# BusBoard.net
KiCad netlist of a schematic drawn in EAGLE
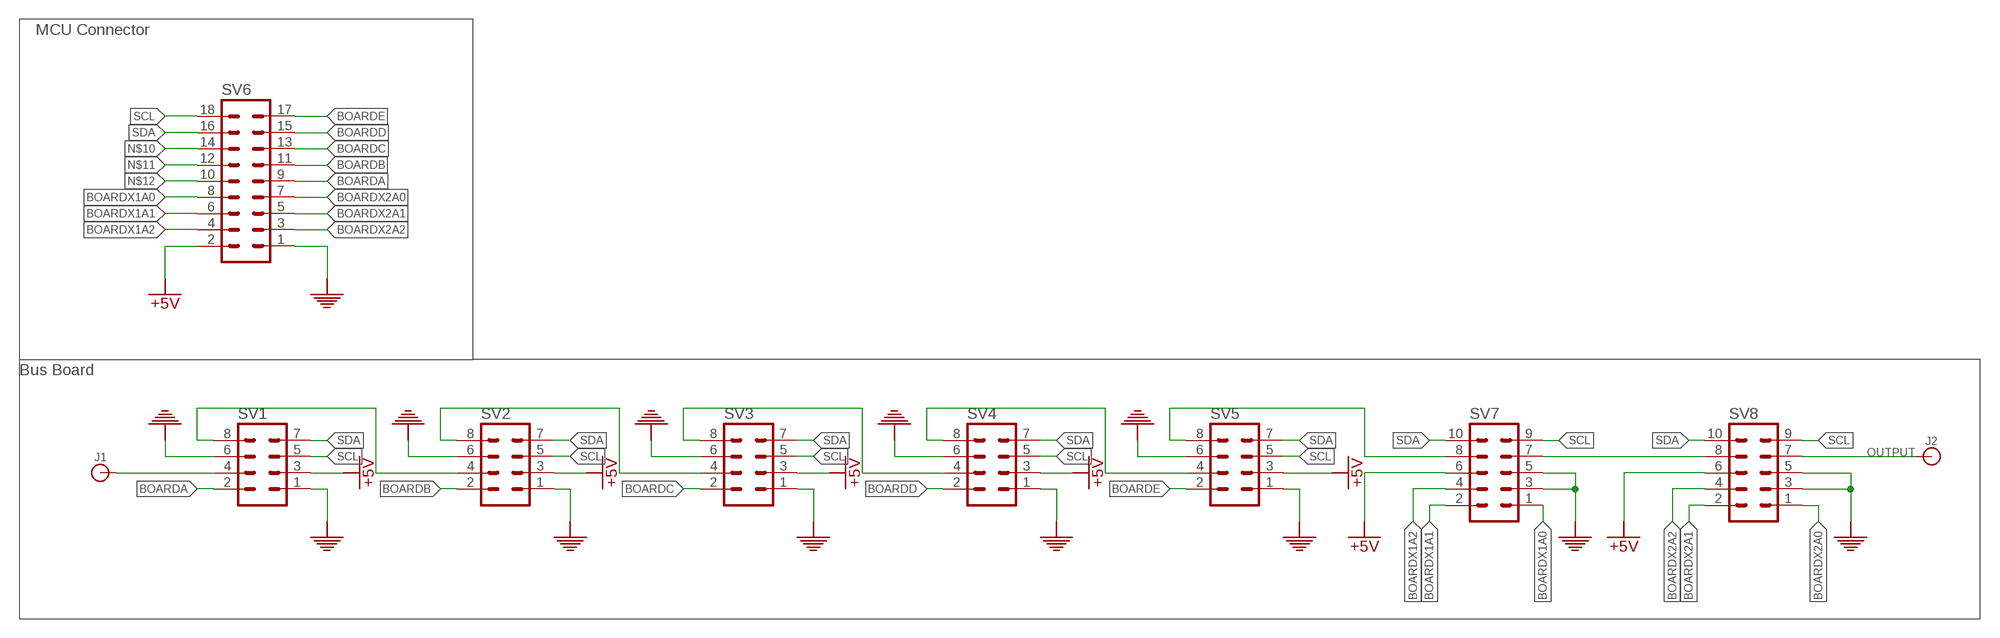
[diagram p0: schematic, sheet 1]

(export (version "E")
  (design (tool "Eeschema 10.0.6"))
  (components
    (comp (ref "J1")
      (value "BANANA_CONN")
      (footprint "eagle-import:BANANA_CONN")
      (libsource (lib "eagle-import") (part "BANANA_CONN"))
    )
    (comp (ref "J2")
      (value "BANANA_CONN")
      (footprint "eagle-import:BANANA_CONN")
      (libsource (lib "eagle-import") (part "BANANA_CONN"))
    )
    (comp (ref "SV1")
      (value "MA04-2")
      (footprint "eagle-import:MA04-2")
      (libsource (lib "eagle-import") (part "MA04-2"))
    )
    (comp (ref "SV2")
      (value "MA04-2")
      (footprint "eagle-import:MA04-2")
      (libsource (lib "eagle-import") (part "MA04-2"))
    )
    (comp (ref "SV3")
      (value "MA04-2")
      (footprint "eagle-import:MA04-2")
      (libsource (lib "eagle-import") (part "MA04-2"))
    )
    (comp (ref "SV4")
      (value "MA04-2")
      (footprint "eagle-import:MA04-2")
      (libsource (lib "eagle-import") (part "MA04-2"))
    )
    (comp (ref "SV5")
      (value "MA04-2")
      (footprint "eagle-import:MA04-2")
      (libsource (lib "eagle-import") (part "MA04-2"))
    )
    (comp (ref "SV6")
      (value "MA09-2")
      (footprint "eagle-import:MA09-2")
      (libsource (lib "eagle-import") (part "MA09-2"))
    )
    (comp (ref "SV7")
      (value "MA05-2")
      (footprint "eagle-import:MA05-2")
      (libsource (lib "eagle-import") (part "MA05-2"))
    )
    (comp (ref "SV8")
      (value "MA05-2")
      (footprint "eagle-import:MA05-2")
      (libsource (lib "eagle-import") (part "MA05-2"))
    )
  )
  (nets
    (net (code "1") (name "+5V") (class "Default")
      (node (ref "SV1") (pin "3") (pinfunction "3_3") (pintype "passive"))
      (node (ref "SV2") (pin "3") (pinfunction "3_3") (pintype "passive"))
      (node (ref "SV3") (pin "3") (pinfunction "3_3") (pintype "passive"))
      (node (ref "SV4") (pin "3") (pinfunction "3_3") (pintype "passive"))
      (node (ref "SV5") (pin "3") (pinfunction "3_3") (pintype "passive"))
      (node (ref "SV6") (pin "2") (pinfunction "2_2") (pintype "passive"))
      (node (ref "SV7") (pin "6") (pinfunction "6_6") (pintype "passive"))
      (node (ref "SV8") (pin "6") (pinfunction "6_6") (pintype "passive"))
    )
    (net (code "2") (name "/OUTPUT") (class "Default")
      (node (ref "J2") (pin "P$1") (pinfunction "1_P$1") (pintype "passive"))
      (node (ref "SV8") (pin "7") (pinfunction "7_7") (pintype "passive"))
    )
    (net (code "3") (name "BOARDA") (class "Default")
      (node (ref "SV1") (pin "2") (pinfunction "2_2") (pintype "passive"))
      (node (ref "SV6") (pin "9") (pinfunction "9_9") (pintype "passive"))
    )
    (net (code "4") (name "BOARDB") (class "Default")
      (node (ref "SV2") (pin "2") (pinfunction "2_2") (pintype "passive"))
      (node (ref "SV6") (pin "11") (pinfunction "11_11") (pintype "passive"))
    )
    (net (code "5") (name "BOARDC") (class "Default")
      (node (ref "SV3") (pin "2") (pinfunction "2_2") (pintype "passive"))
      (node (ref "SV6") (pin "13") (pinfunction "13_13") (pintype "passive"))
    )
    (net (code "6") (name "BOARDD") (class "Default")
      (node (ref "SV4") (pin "2") (pinfunction "2_2") (pintype "passive"))
      (node (ref "SV6") (pin "15") (pinfunction "15_15") (pintype "passive"))
    )
    (net (code "7") (name "BOARDE") (class "Default")
      (node (ref "SV5") (pin "2") (pinfunction "2_2") (pintype "passive"))
      (node (ref "SV6") (pin "17") (pinfunction "17_17") (pintype "passive"))
    )
    (net (code "8") (name "BOARDX1A0") (class "Default")
      (node (ref "SV6") (pin "8") (pinfunction "8_8") (pintype "passive"))
      (node (ref "SV7") (pin "1") (pinfunction "1_1") (pintype "passive"))
    )
    (net (code "9") (name "BOARDX1A1") (class "Default")
      (node (ref "SV6") (pin "6") (pinfunction "6_6") (pintype "passive"))
      (node (ref "SV7") (pin "2") (pinfunction "2_2") (pintype "passive"))
    )
    (net (code "10") (name "BOARDX1A2") (class "Default")
      (node (ref "SV6") (pin "4") (pinfunction "4_4") (pintype "passive"))
      (node (ref "SV7") (pin "4") (pinfunction "4_4") (pintype "passive"))
    )
    (net (code "11") (name "BOARDX2A0") (class "Default")
      (node (ref "SV6") (pin "7") (pinfunction "7_7") (pintype "passive"))
      (node (ref "SV8") (pin "1") (pinfunction "1_1") (pintype "passive"))
    )
    (net (code "12") (name "BOARDX2A1") (class "Default")
      (node (ref "SV6") (pin "5") (pinfunction "5_5") (pintype "passive"))
      (node (ref "SV8") (pin "2") (pinfunction "2_2") (pintype "passive"))
    )
    (net (code "13") (name "BOARDX2A2") (class "Default")
      (node (ref "SV6") (pin "3") (pinfunction "3_3") (pintype "passive"))
      (node (ref "SV8") (pin "4") (pinfunction "4_4") (pintype "passive"))
    )
    (net (code "14") (name "GND") (class "Default")
      (node (ref "SV1") (pin "1") (pinfunction "1_1") (pintype "passive"))
      (node (ref "SV1") (pin "6") (pinfunction "6_6") (pintype "passive"))
      (node (ref "SV2") (pin "1") (pinfunction "1_1") (pintype "passive"))
      (node (ref "SV2") (pin "6") (pinfunction "6_6") (pintype "passive"))
      (node (ref "SV3") (pin "1") (pinfunction "1_1") (pintype "passive"))
      (node (ref "SV3") (pin "6") (pinfunction "6_6") (pintype "passive"))
      (node (ref "SV4") (pin "1") (pinfunction "1_1") (pintype "passive"))
      (node (ref "SV4") (pin "6") (pinfunction "6_6") (pintype "passive"))
      (node (ref "SV5") (pin "1") (pinfunction "1_1") (pintype "passive"))
      (node (ref "SV5") (pin "6") (pinfunction "6_6") (pintype "passive"))
      (node (ref "SV6") (pin "1") (pinfunction "1_1") (pintype "passive"))
      (node (ref "SV7") (pin "3") (pinfunction "3_3") (pintype "passive"))
      (node (ref "SV7") (pin "5") (pinfunction "5_5") (pintype "passive"))
      (node (ref "SV8") (pin "3") (pinfunction "3_3") (pintype "passive"))
      (node (ref "SV8") (pin "5") (pinfunction "5_5") (pintype "passive"))
    )
    (net (code "15") (name "N$10") (class "Default")
      (node (ref "SV6") (pin "14") (pinfunction "14_14") (pintype "passive"))
    )
    (net (code "16") (name "N$11") (class "Default")
      (node (ref "SV6") (pin "12") (pinfunction "12_12") (pintype "passive"))
    )
    (net (code "17") (name "N$12") (class "Default")
      (node (ref "SV6") (pin "10") (pinfunction "10_10") (pintype "passive"))
    )
    (net (code "18") (name "Net-(J1-1)") (class "Default")
      (node (ref "J1") (pin "P$1") (pinfunction "1_P$1") (pintype "passive"))
      (node (ref "SV1") (pin "4") (pinfunction "4_4") (pintype "passive"))
    )
    (net (code "19") (name "Net-(SV1-Pad8)") (class "Default")
      (node (ref "SV1") (pin "8") (pinfunction "8_8") (pintype "passive"))
      (node (ref "SV2") (pin "4") (pinfunction "4_4") (pintype "passive"))
    )
    (net (code "20") (name "Net-(SV2-Pad8)") (class "Default")
      (node (ref "SV2") (pin "8") (pinfunction "8_8") (pintype "passive"))
      (node (ref "SV3") (pin "4") (pinfunction "4_4") (pintype "passive"))
    )
    (net (code "21") (name "Net-(SV3-Pad8)") (class "Default")
      (node (ref "SV3") (pin "8") (pinfunction "8_8") (pintype "passive"))
      (node (ref "SV4") (pin "4") (pinfunction "4_4") (pintype "passive"))
    )
    (net (code "22") (name "Net-(SV4-Pad8)") (class "Default")
      (node (ref "SV4") (pin "8") (pinfunction "8_8") (pintype "passive"))
      (node (ref "SV5") (pin "4") (pinfunction "4_4") (pintype "passive"))
    )
    (net (code "23") (name "Net-(SV5-Pad8)") (class "Default")
      (node (ref "SV5") (pin "8") (pinfunction "8_8") (pintype "passive"))
      (node (ref "SV7") (pin "8") (pinfunction "8_8") (pintype "passive"))
    )
    (net (code "24") (name "Net-(SV7-Pad7)") (class "Default")
      (node (ref "SV7") (pin "7") (pinfunction "7_7") (pintype "passive"))
      (node (ref "SV8") (pin "8") (pinfunction "8_8") (pintype "passive"))
    )
    (net (code "25") (name "SCL") (class "Default")
      (node (ref "SV1") (pin "5") (pinfunction "5_5") (pintype "passive"))
      (node (ref "SV2") (pin "5") (pinfunction "5_5") (pintype "passive"))
      (node (ref "SV3") (pin "5") (pinfunction "5_5") (pintype "passive"))
      (node (ref "SV4") (pin "5") (pinfunction "5_5") (pintype "passive"))
      (node (ref "SV5") (pin "5") (pinfunction "5_5") (pintype "passive"))
      (node (ref "SV6") (pin "18") (pinfunction "18_18") (pintype "passive"))
      (node (ref "SV7") (pin "9") (pinfunction "9_9") (pintype "passive"))
      (node (ref "SV8") (pin "9") (pinfunction "9_9") (pintype "passive"))
    )
    (net (code "26") (name "SDA") (class "Default")
      (node (ref "SV1") (pin "7") (pinfunction "7_7") (pintype "passive"))
      (node (ref "SV2") (pin "7") (pinfunction "7_7") (pintype "passive"))
      (node (ref "SV3") (pin "7") (pinfunction "7_7") (pintype "passive"))
      (node (ref "SV4") (pin "7") (pinfunction "7_7") (pintype "passive"))
      (node (ref "SV5") (pin "7") (pinfunction "7_7") (pintype "passive"))
      (node (ref "SV6") (pin "16") (pinfunction "16_16") (pintype "passive"))
      (node (ref "SV7") (pin "10") (pinfunction "10_10") (pintype "passive"))
      (node (ref "SV8") (pin "10") (pinfunction "10_10") (pintype "passive"))
    )
  )
)
